# SelfBus_JTAG_SWD_Adapter.net
KiCad netlist of a schematic drawn in EAGLE
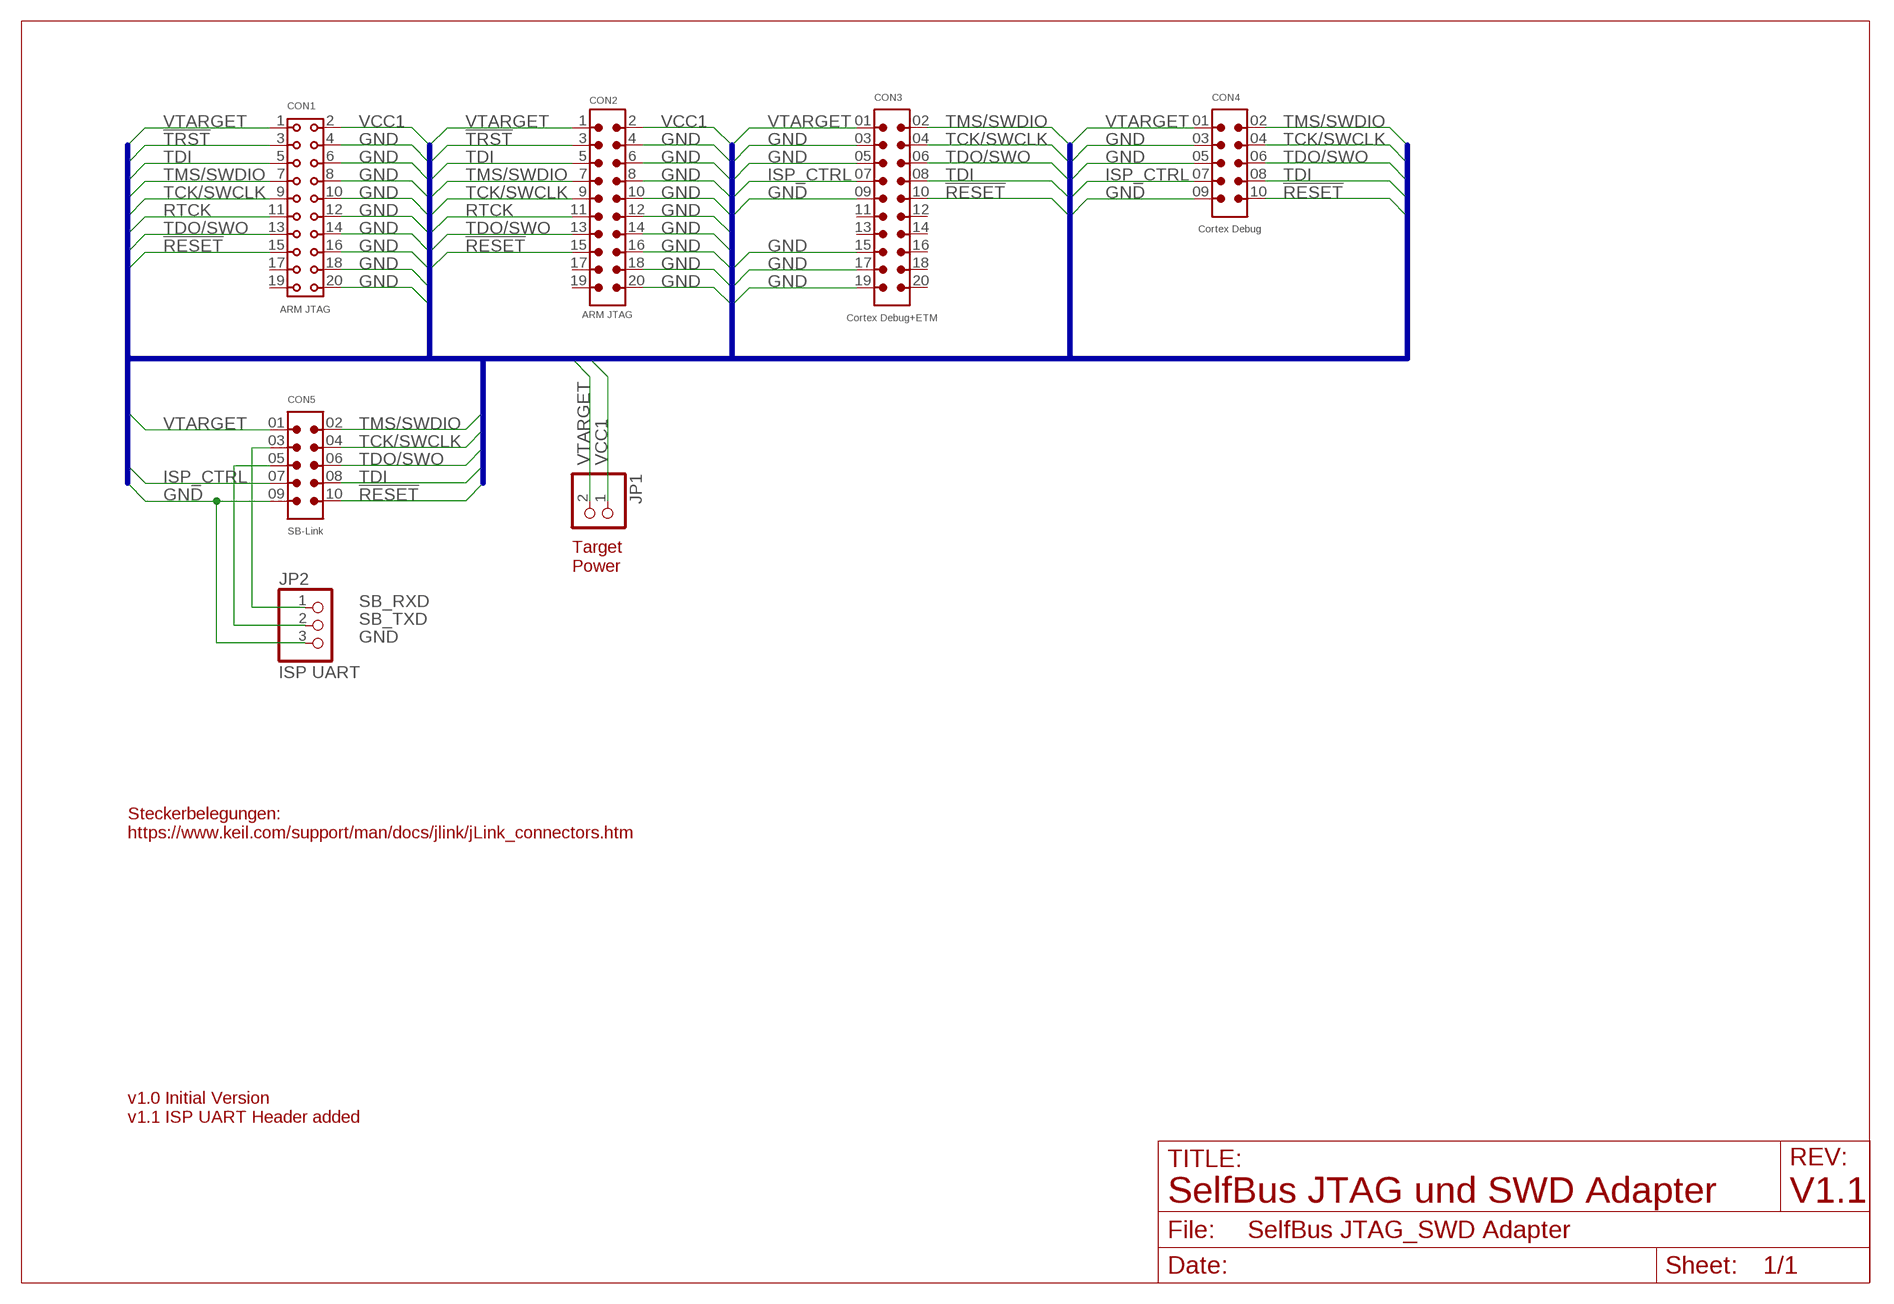
[diagram p0: schematic, sheet 1]

(export (version "E")
  (design (tool "Eeschema 10.0.6"))
  (components
    (comp (ref "CON1")
      (value "ARM JTAG")
      (footprint "eagle-import:SAMTEC-SSQ-110-02-X-D-RA")
      (fields (field (name "PART#") "Samtec SSQ-110-02-T-D-RA"))
      (libsource (lib "eagle-import") (part "SAMTEC-SSQ-110-02-X-D-RA"))
    )
    (comp (ref "CON2")
      (value "ARM JTAG")
      (footprint "eagle-import:61202021721")
      (fields (field (name "PART#") "Würth 61202021721"))
      (libsource (lib "eagle-import") (part "6120XX21721_61202021721"))
    )
    (comp (ref "CON3")
      (value "Cortex Debug+ETM")
      (footprint "eagle-import:SAMTEC_SHF-110-01-L-D-TH")
      (fields (field (name "PART#") "SHF-110-01-L-D-TH"))
      (libsource (lib "eagle-import") (part "SHF-110-01-L-D-TH"))
    )
    (comp (ref "CON4")
      (value "Cortex Debug")
      (footprint "eagle-import:SAMTEC_SHF-105-01-X-D-TH")
      (fields (field (name "PART#") "SHF-105-01-L-D-TH"))
      (libsource (lib "eagle-import") (part "SHF-105-01-X-D-TH"))
    )
    (comp (ref "CON5")
      (value "SB-Link")
      (footprint "eagle-import:SAMTEC-LTMM-105-02-T-D")
      (fields (field (name "PART#") "Samtec LTMM-105-02-T-D"))
      (libsource (lib "eagle-import") (part "SAMTEC-LTMM-105-02-T-D"))
    )
    (comp (ref "JP1")
      (value "Target Power")
      (footprint "eagle-import:1X02")
      (libsource (lib "eagle-import") (part "PINHD-1X2"))
    )
    (comp (ref "JP2")
      (value "ISP UART")
      (footprint "eagle-import:1X03")
      (libsource (lib "eagle-import") (part "PINHD-1X3"))
    )
  )
  (nets
    (net (code "1") (name "/GND") (class "Default")
      (node (ref "CON1") (pin "10") (pinfunction "10_10") (pintype "passive"))
      (node (ref "CON1") (pin "12") (pinfunction "12_12") (pintype "passive"))
      (node (ref "CON1") (pin "14") (pinfunction "14_14") (pintype "passive"))
      (node (ref "CON1") (pin "16") (pinfunction "16_16") (pintype "passive"))
      (node (ref "CON1") (pin "18") (pinfunction "18_18") (pintype "passive"))
      (node (ref "CON1") (pin "20") (pinfunction "20_20") (pintype "passive"))
      (node (ref "CON1") (pin "4") (pinfunction "4_4") (pintype "passive"))
      (node (ref "CON1") (pin "6") (pinfunction "6_6") (pintype "passive"))
      (node (ref "CON1") (pin "8") (pinfunction "8_8") (pintype "passive"))
      (node (ref "CON2") (pin "10") (pinfunction "10_10") (pintype "passive"))
      (node (ref "CON2") (pin "12") (pinfunction "12_12") (pintype "passive"))
      (node (ref "CON2") (pin "14") (pinfunction "14_14") (pintype "passive"))
      (node (ref "CON2") (pin "16") (pinfunction "16_16") (pintype "passive"))
      (node (ref "CON2") (pin "18") (pinfunction "18_18") (pintype "passive"))
      (node (ref "CON2") (pin "20") (pinfunction "20_20") (pintype "passive"))
      (node (ref "CON2") (pin "4") (pinfunction "4_4") (pintype "passive"))
      (node (ref "CON2") (pin "6") (pinfunction "6_6") (pintype "passive"))
      (node (ref "CON2") (pin "8") (pinfunction "8_8") (pintype "passive"))
      (node (ref "CON3") (pin "03") (pinfunction "3_03") (pintype "passive"))
      (node (ref "CON3") (pin "05") (pinfunction "5_05") (pintype "passive"))
      (node (ref "CON3") (pin "09") (pinfunction "9_09") (pintype "passive"))
      (node (ref "CON3") (pin "15") (pinfunction "15_15") (pintype "passive"))
      (node (ref "CON3") (pin "17") (pinfunction "17_17") (pintype "passive"))
      (node (ref "CON3") (pin "19") (pinfunction "19_19") (pintype "passive"))
      (node (ref "CON4") (pin "03") (pinfunction "3_03") (pintype "passive"))
      (node (ref "CON4") (pin "05") (pinfunction "5_05") (pintype "passive"))
      (node (ref "CON4") (pin "09") (pinfunction "9_09") (pintype "passive"))
      (node (ref "CON5") (pin "09") (pinfunction "9_09") (pintype "passive"))
      (node (ref "JP2") (pin "3") (pinfunction "3_3") (pintype "passive"))
    )
    (net (code "2") (name "/ISP_CTRL") (class "Default")
      (node (ref "CON3") (pin "07") (pinfunction "7_07") (pintype "passive"))
      (node (ref "CON4") (pin "07") (pinfunction "7_07") (pintype "passive"))
      (node (ref "CON5") (pin "07") (pinfunction "7_07") (pintype "passive"))
    )
    (net (code "3") (name "/RTCK") (class "Default")
      (node (ref "CON1") (pin "11") (pinfunction "11_11") (pintype "passive"))
      (node (ref "CON2") (pin "11") (pinfunction "11_11") (pintype "passive"))
    )
    (net (code "4") (name "/SB_RXD") (class "Default")
      (node (ref "CON5") (pin "03") (pinfunction "3_03") (pintype "passive"))
      (node (ref "JP2") (pin "1") (pinfunction "1_1") (pintype "passive"))
    )
    (net (code "5") (name "/SB_TXD") (class "Default")
      (node (ref "CON5") (pin "05") (pinfunction "5_05") (pintype "passive"))
      (node (ref "JP2") (pin "2") (pinfunction "2_2") (pintype "passive"))
    )
    (net (code "6") (name "/TCK{slash}SWCLK") (class "Default")
      (node (ref "CON1") (pin "9") (pinfunction "9_9") (pintype "passive"))
      (node (ref "CON2") (pin "9") (pinfunction "9_9") (pintype "passive"))
      (node (ref "CON3") (pin "04") (pinfunction "4_04") (pintype "passive"))
      (node (ref "CON4") (pin "04") (pinfunction "4_04") (pintype "passive"))
      (node (ref "CON5") (pin "04") (pinfunction "4_04") (pintype "passive"))
    )
    (net (code "7") (name "/TDI") (class "Default")
      (node (ref "CON1") (pin "5") (pinfunction "5_5") (pintype "passive"))
      (node (ref "CON2") (pin "5") (pinfunction "5_5") (pintype "passive"))
      (node (ref "CON3") (pin "08") (pinfunction "8_08") (pintype "passive"))
      (node (ref "CON4") (pin "08") (pinfunction "8_08") (pintype "passive"))
      (node (ref "CON5") (pin "08") (pinfunction "8_08") (pintype "passive"))
    )
    (net (code "8") (name "/TDO{slash}SWO") (class "Default")
      (node (ref "CON1") (pin "13") (pinfunction "13_13") (pintype "passive"))
      (node (ref "CON2") (pin "13") (pinfunction "13_13") (pintype "passive"))
      (node (ref "CON3") (pin "06") (pinfunction "6_06") (pintype "passive"))
      (node (ref "CON4") (pin "06") (pinfunction "6_06") (pintype "passive"))
      (node (ref "CON5") (pin "06") (pinfunction "6_06") (pintype "passive"))
    )
    (net (code "9") (name "/TMS{slash}SWDIO") (class "Default")
      (node (ref "CON1") (pin "7") (pinfunction "7_7") (pintype "passive"))
      (node (ref "CON2") (pin "7") (pinfunction "7_7") (pintype "passive"))
      (node (ref "CON3") (pin "02") (pinfunction "2_02") (pintype "passive"))
      (node (ref "CON4") (pin "02") (pinfunction "2_02") (pintype "passive"))
      (node (ref "CON5") (pin "02") (pinfunction "2_02") (pintype "passive"))
    )
    (net (code "10") (name "/VCC1") (class "Default")
      (node (ref "CON1") (pin "2") (pinfunction "2_2") (pintype "passive"))
      (node (ref "CON2") (pin "2") (pinfunction "2_2") (pintype "passive"))
      (node (ref "JP1") (pin "1") (pinfunction "1_1") (pintype "passive"))
    )
    (net (code "11") (name "/VTARGET") (class "Default")
      (node (ref "CON1") (pin "1") (pinfunction "1_1") (pintype "passive"))
      (node (ref "CON2") (pin "1") (pinfunction "1_1") (pintype "passive"))
      (node (ref "CON3") (pin "01") (pinfunction "1_01") (pintype "passive"))
      (node (ref "CON4") (pin "01") (pinfunction "1_01") (pintype "passive"))
      (node (ref "CON5") (pin "01") (pinfunction "1_01") (pintype "passive"))
      (node (ref "JP1") (pin "2") (pinfunction "2_2") (pintype "passive"))
    )
    (net (code "12") (name "/~{RESET}") (class "Default")
      (node (ref "CON1") (pin "15") (pinfunction "15_15") (pintype "passive"))
      (node (ref "CON2") (pin "15") (pinfunction "15_15") (pintype "passive"))
      (node (ref "CON3") (pin "10") (pinfunction "10_10") (pintype "passive"))
      (node (ref "CON4") (pin "10") (pinfunction "10_10") (pintype "passive"))
      (node (ref "CON5") (pin "10") (pinfunction "10_10") (pintype "passive"))
    )
    (net (code "13") (name "/~{TRST}") (class "Default")
      (node (ref "CON1") (pin "3") (pinfunction "3_3") (pintype "passive"))
      (node (ref "CON2") (pin "3") (pinfunction "3_3") (pintype "passive"))
    )
    (net (code "14") (name "unconnected-(CON1-Pad17)") (class "Default")
      (node (ref "CON1") (pin "17") (pinfunction "17_17") (pintype "passive"))
    )
    (net (code "15") (name "unconnected-(CON1-Pad19)") (class "Default")
      (node (ref "CON1") (pin "19") (pinfunction "19_19") (pintype "passive"))
    )
    (net (code "16") (name "unconnected-(CON2-Pad17)") (class "Default")
      (node (ref "CON2") (pin "17") (pinfunction "17_17") (pintype "passive"))
    )
    (net (code "17") (name "unconnected-(CON2-Pad19)") (class "Default")
      (node (ref "CON2") (pin "19") (pinfunction "19_19") (pintype "passive"))
    )
    (net (code "18") (name "unconnected-(CON3-Pad11)") (class "Default")
      (node (ref "CON3") (pin "11") (pinfunction "11_11") (pintype "passive"))
    )
    (net (code "19") (name "unconnected-(CON3-Pad12)") (class "Default")
      (node (ref "CON3") (pin "12") (pinfunction "12_12") (pintype "passive"))
    )
    (net (code "20") (name "unconnected-(CON3-Pad13)") (class "Default")
      (node (ref "CON3") (pin "13") (pinfunction "13_13") (pintype "passive"))
    )
    (net (code "21") (name "unconnected-(CON3-Pad14)") (class "Default")
      (node (ref "CON3") (pin "14") (pinfunction "14_14") (pintype "passive"))
    )
    (net (code "22") (name "unconnected-(CON3-Pad16)") (class "Default")
      (node (ref "CON3") (pin "16") (pinfunction "16_16") (pintype "passive"))
    )
    (net (code "23") (name "unconnected-(CON3-Pad18)") (class "Default")
      (node (ref "CON3") (pin "18") (pinfunction "18_18") (pintype "passive"))
    )
    (net (code "24") (name "unconnected-(CON3-Pad20)") (class "Default")
      (node (ref "CON3") (pin "20") (pinfunction "20_20") (pintype "passive"))
    )
  )
)
